# USB.net
KiCad netlist of a schematic drawn in Altium Designer
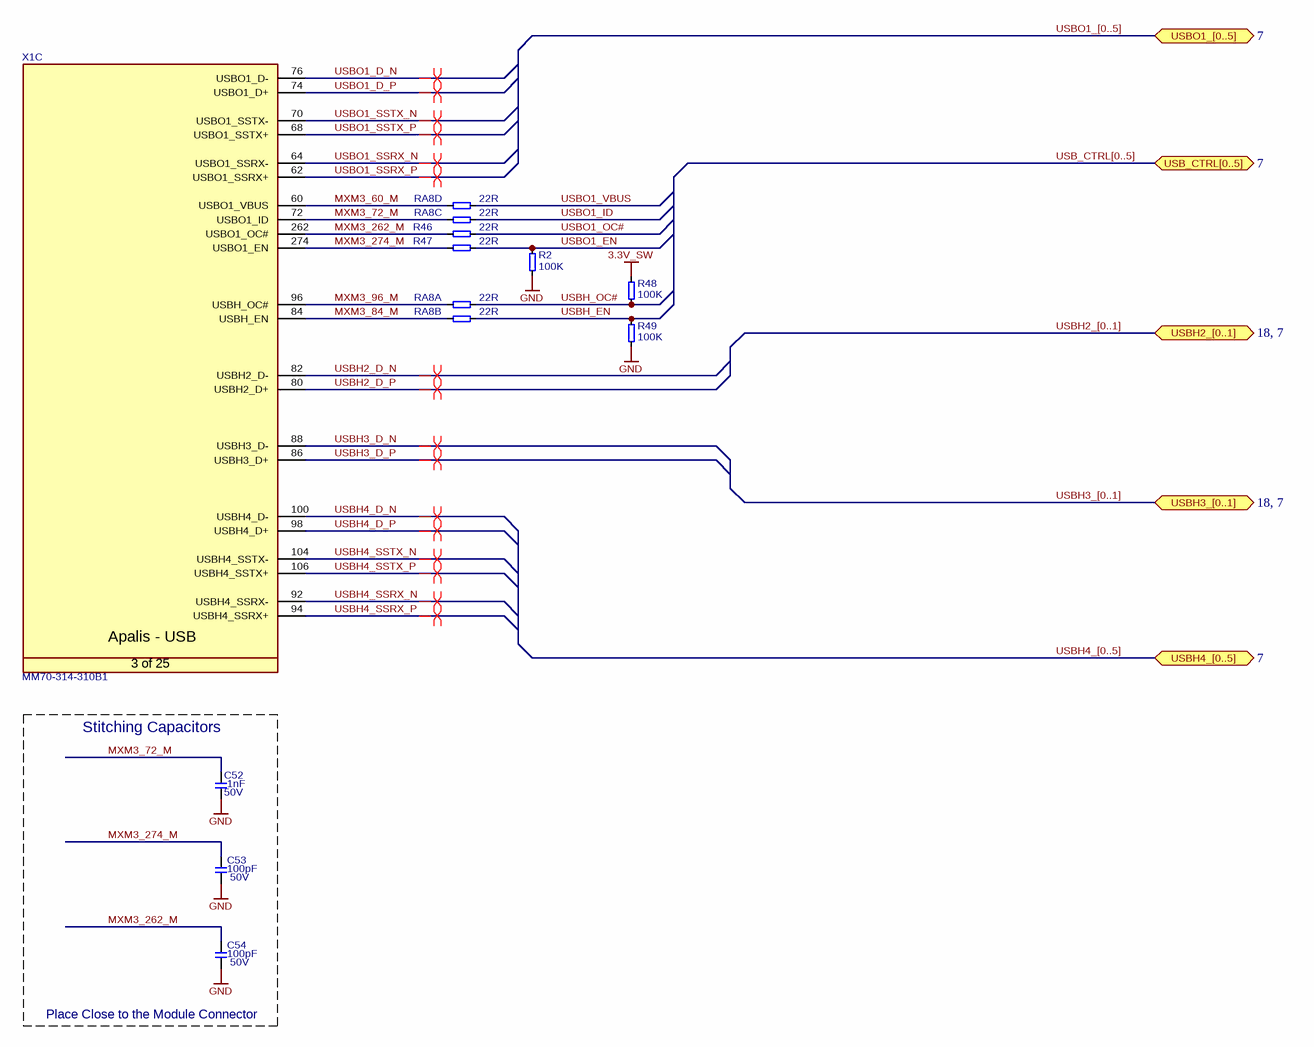
[diagram p0: USB.SchDoc]

(export (version "E")
  (design (tool "Eeschema 10.0.6"))
  (components
    (comp (ref "C52")
      (value "1nF")
      (footprint "CAPC1005X60N")
      (description "Capacitor Ceramic X7R 1nF 50V 10% 0402")
      (fields (field (name "TOLERANCE") "10%") (field (name "RATING") "50V"))
      (libsource (lib "Ixora") (part "C-X7R-1nF-50V-10%-0402"))
    )
    (comp (ref "C53")
      (value "100pF")
      (footprint "CAPC1005X60N")
      (description "Capacitor Ceramic X7R 100pF 50V 10% 0402")
      (fields (field (name "TOLERANCE") "10%") (field (name "RATING") "50V"))
      (libsource (lib "Ixora") (part "C-X7R-100pF-50V-10%-0402"))
    )
    (comp (ref "C54")
      (value "100pF")
      (footprint "CAPC1005X60N")
      (description "Capacitor Ceramic X7R 100pF 50V 10% 0402")
      (fields (field (name "TOLERANCE") "10%") (field (name "RATING") "50V"))
      (libsource (lib "Ixora") (part "C-X7R-100pF-50V-10%-0402"))
    )
    (comp (ref "R2")
      (value "100K")
      (footprint "RESC1005X40N")
      (description "Resistor 100 Kohm 63mW 5% 0402")
      (fields (field (name "TOLERANCE") "5%"))
      (libsource (lib "Ixora") (part "R-100KR-63mW-5%-0402"))
    )
    (comp (ref "R46")
      (value "22R")
      (footprint "RESC1005X40N")
      (description "Resistor 22 ohm 63mW 5% 0402")
      (fields (field (name "TOLERANCE") "5%"))
      (libsource (lib "Ixora") (part "R-22R-63mW-5%-0402"))
    )
    (comp (ref "R47")
      (value "22R")
      (footprint "RESC1005X40N")
      (description "Resistor 22 ohm 63mW 5% 0402")
      (fields (field (name "TOLERANCE") "5%"))
      (libsource (lib "Ixora") (part "R-22R-63mW-5%-0402"))
    )
    (comp (ref "R48")
      (value "100K")
      (footprint "RESC1005X40N")
      (description "Resistor 100 Kohm 63mW 5% 0402")
      (fields (field (name "TOLERANCE") "5%"))
      (libsource (lib "Ixora") (part "R-100KR-63mW-5%-0402"))
    )
    (comp (ref "R49")
      (value "100K")
      (footprint "RESC1005X40N")
      (description "Resistor 100 Kohm 63mW 5% 0402")
      (fields (field (name "TOLERANCE") "5%"))
      (libsource (lib "Ixora") (part "R-100KR-63mW-5%-0402"))
    )
    (comp (ref "RA8")
      (value "22R")
      (footprint "T_Resistor_Array_X4")
      (description "Resistor Array 22 R 63mW 5% 1206")
      (fields (field (name "TOLERANCE") "5%"))
      (libsource (lib "Ixora") (part "RA-22R-63mW-5%-1206-div"))
    )
    (comp (ref "X1")
      (value "CON-JAE-MM70-314-310B1-314-0.5mm")
      (footprint "T_JAE_MM70-314-310B1")
      (description "MXM3 Connector")
      (fields (field (name "MANUFACTURER PART NO.") "MM70-314-310B1"))
      (libsource (lib "Ixora") (part "CON-JAE-MM70-314-310B1-314-0.5mm"))
    )
  )
  (nets
    (net (code "23") (name "/MXM3_60_M") (class "Default")
      (node (ref "RA8") (pin "4") (pinfunction "4_4") (pintype "passive"))
      (node (ref "X1") (pin "60") (pinfunction "USBO1_VBUS_60") (pintype "passive"))
    )
    (net (code "24") (name "/MXM3_72_M") (class "Default")
      (node (ref "C52") (pin "2") (pinfunction "2_2") (pintype "passive"))
      (node (ref "RA8") (pin "3") (pinfunction "3_3") (pintype "passive"))
      (node (ref "X1") (pin "72") (pinfunction "USBO1_ID_72") (pintype "passive"))
    )
    (net (code "25") (name "/MXM3_84_M") (class "Default")
      (node (ref "RA8") (pin "2") (pinfunction "2_2") (pintype "passive"))
      (node (ref "X1") (pin "84") (pinfunction "USBH_EN_84") (pintype "passive"))
    )
    (net (code "26") (name "/MXM3_96_M") (class "Default")
      (node (ref "RA8") (pin "1") (pinfunction "1_1") (pintype "passive"))
      (node (ref "X1") (pin "96") (pinfunction "USBH_OC#_96") (pintype "passive"))
    )
    (net (code "27") (name "/MXM3_262_M") (class "Default")
      (node (ref "C54") (pin "2") (pinfunction "2_2") (pintype "passive"))
      (node (ref "R46") (pin "1") (pinfunction "1_1") (pintype "passive"))
      (node (ref "X1") (pin "262") (pinfunction "USBO1_OC#_262") (pintype "passive"))
    )
    (net (code "28") (name "/MXM3_274_M") (class "Default")
      (node (ref "C53") (pin "2") (pinfunction "2_2") (pintype "passive"))
      (node (ref "R47") (pin "1") (pinfunction "1_1") (pintype "passive"))
      (node (ref "X1") (pin "274") (pinfunction "USBO1_EN_274") (pintype "passive"))
    )
    (net (code "29") (name "/USBH2_D_N") (class "Default")
      (node (ref "X1") (pin "82") (pinfunction "USBH2_D-_82") (pintype "passive"))
    )
    (net (code "30") (name "/USBH2_D_P") (class "Default")
      (node (ref "X1") (pin "80") (pinfunction "USBH2_D+_80") (pintype "passive"))
    )
    (net (code "32") (name "/USBH3_D_N") (class "Default")
      (node (ref "X1") (pin "88") (pinfunction "USBH3_D-_88") (pintype "passive"))
    )
    (net (code "33") (name "/USBH3_D_P") (class "Default")
      (node (ref "X1") (pin "86") (pinfunction "USBH3_D+_86") (pintype "passive"))
    )
    (net (code "35") (name "/USBH4_D_N") (class "Default")
      (node (ref "X1") (pin "100") (pinfunction "USBH4_D-_100") (pintype "passive"))
    )
    (net (code "36") (name "/USBH4_D_P") (class "Default")
      (node (ref "X1") (pin "98") (pinfunction "USBH4_D+_98") (pintype "passive"))
    )
    (net (code "37") (name "/USBH4_SSRX_N") (class "Default")
      (node (ref "X1") (pin "92") (pinfunction "USBH4_SSRX-_92") (pintype "passive"))
    )
    (net (code "38") (name "/USBH4_SSRX_P") (class "Default")
      (node (ref "X1") (pin "94") (pinfunction "USBH4_SSRX+_94") (pintype "passive"))
    )
    (net (code "39") (name "/USBH4_SSTX_N") (class "Default")
      (node (ref "X1") (pin "104") (pinfunction "USBH4_SSTX-_104") (pintype "passive"))
    )
    (net (code "40") (name "/USBH4_SSTX_P") (class "Default")
      (node (ref "X1") (pin "106") (pinfunction "USBH4_SSTX+_106") (pintype "passive"))
    )
    (net (code "42") (name "/USBH_EN") (class "Default")
      (node (ref "R49") (pin "2") (pinfunction "2_2") (pintype "passive"))
      (node (ref "RA8") (pin "6") (pinfunction "6_6") (pintype "passive"))
    )
    (net (code "43") (name "/USBH_OC#") (class "Default")
      (node (ref "R48") (pin "2") (pinfunction "2_2") (pintype "passive"))
      (node (ref "RA8") (pin "5") (pinfunction "5_5") (pintype "passive"))
    )
    (net (code "44") (name "/USBO1_D_N") (class "Default")
      (node (ref "X1") (pin "76") (pinfunction "USBO1_D-_76") (pintype "passive"))
    )
    (net (code "45") (name "/USBO1_D_P") (class "Default")
      (node (ref "X1") (pin "74") (pinfunction "USBO1_D+_74") (pintype "passive"))
    )
    (net (code "46") (name "/USBO1_EN") (class "Default")
      (node (ref "R2") (pin "2") (pinfunction "2_2") (pintype "passive"))
      (node (ref "R47") (pin "2") (pinfunction "2_2") (pintype "passive"))
    )
    (net (code "47") (name "/USBO1_ID") (class "Default")
      (node (ref "RA8") (pin "7") (pinfunction "7_7") (pintype "passive"))
    )
    (net (code "48") (name "/USBO1_OC#") (class "Default")
      (node (ref "R46") (pin "2") (pinfunction "2_2") (pintype "passive"))
    )
    (net (code "49") (name "/USBO1_SSRX_N") (class "Default")
      (node (ref "X1") (pin "64") (pinfunction "USBO1_SSRX-_64") (pintype "passive"))
    )
    (net (code "50") (name "/USBO1_SSRX_P") (class "Default")
      (node (ref "X1") (pin "62") (pinfunction "USBO1_SSRX+_62") (pintype "passive"))
    )
    (net (code "51") (name "/USBO1_SSTX_N") (class "Default")
      (node (ref "X1") (pin "70") (pinfunction "USBO1_SSTX-_70") (pintype "passive"))
    )
    (net (code "52") (name "/USBO1_SSTX_P") (class "Default")
      (node (ref "X1") (pin "68") (pinfunction "USBO1_SSTX+_68") (pintype "passive"))
    )
    (net (code "53") (name "/USBO1_VBUS") (class "Default")
      (node (ref "RA8") (pin "8") (pinfunction "8_8") (pintype "passive"))
    )
    (net (code "56") (name "3.3V_SW") (class "Default")
      (node (ref "R48") (pin "1") (pinfunction "1_1") (pintype "passive"))
    )
    (net (code "57") (name "GND") (class "Default")
      (node (ref "C52") (pin "1") (pinfunction "1_1") (pintype "passive"))
      (node (ref "C53") (pin "1") (pinfunction "1_1") (pintype "passive"))
      (node (ref "C54") (pin "1") (pinfunction "1_1") (pintype "passive"))
      (node (ref "R2") (pin "1") (pinfunction "1_1") (pintype "passive"))
      (node (ref "R49") (pin "1") (pinfunction "1_1") (pintype "passive"))
    )
  )
)
